# SW6208_A_A_B_LED__188.net
KiCad netlist of a schematic drawn in Altium Designer
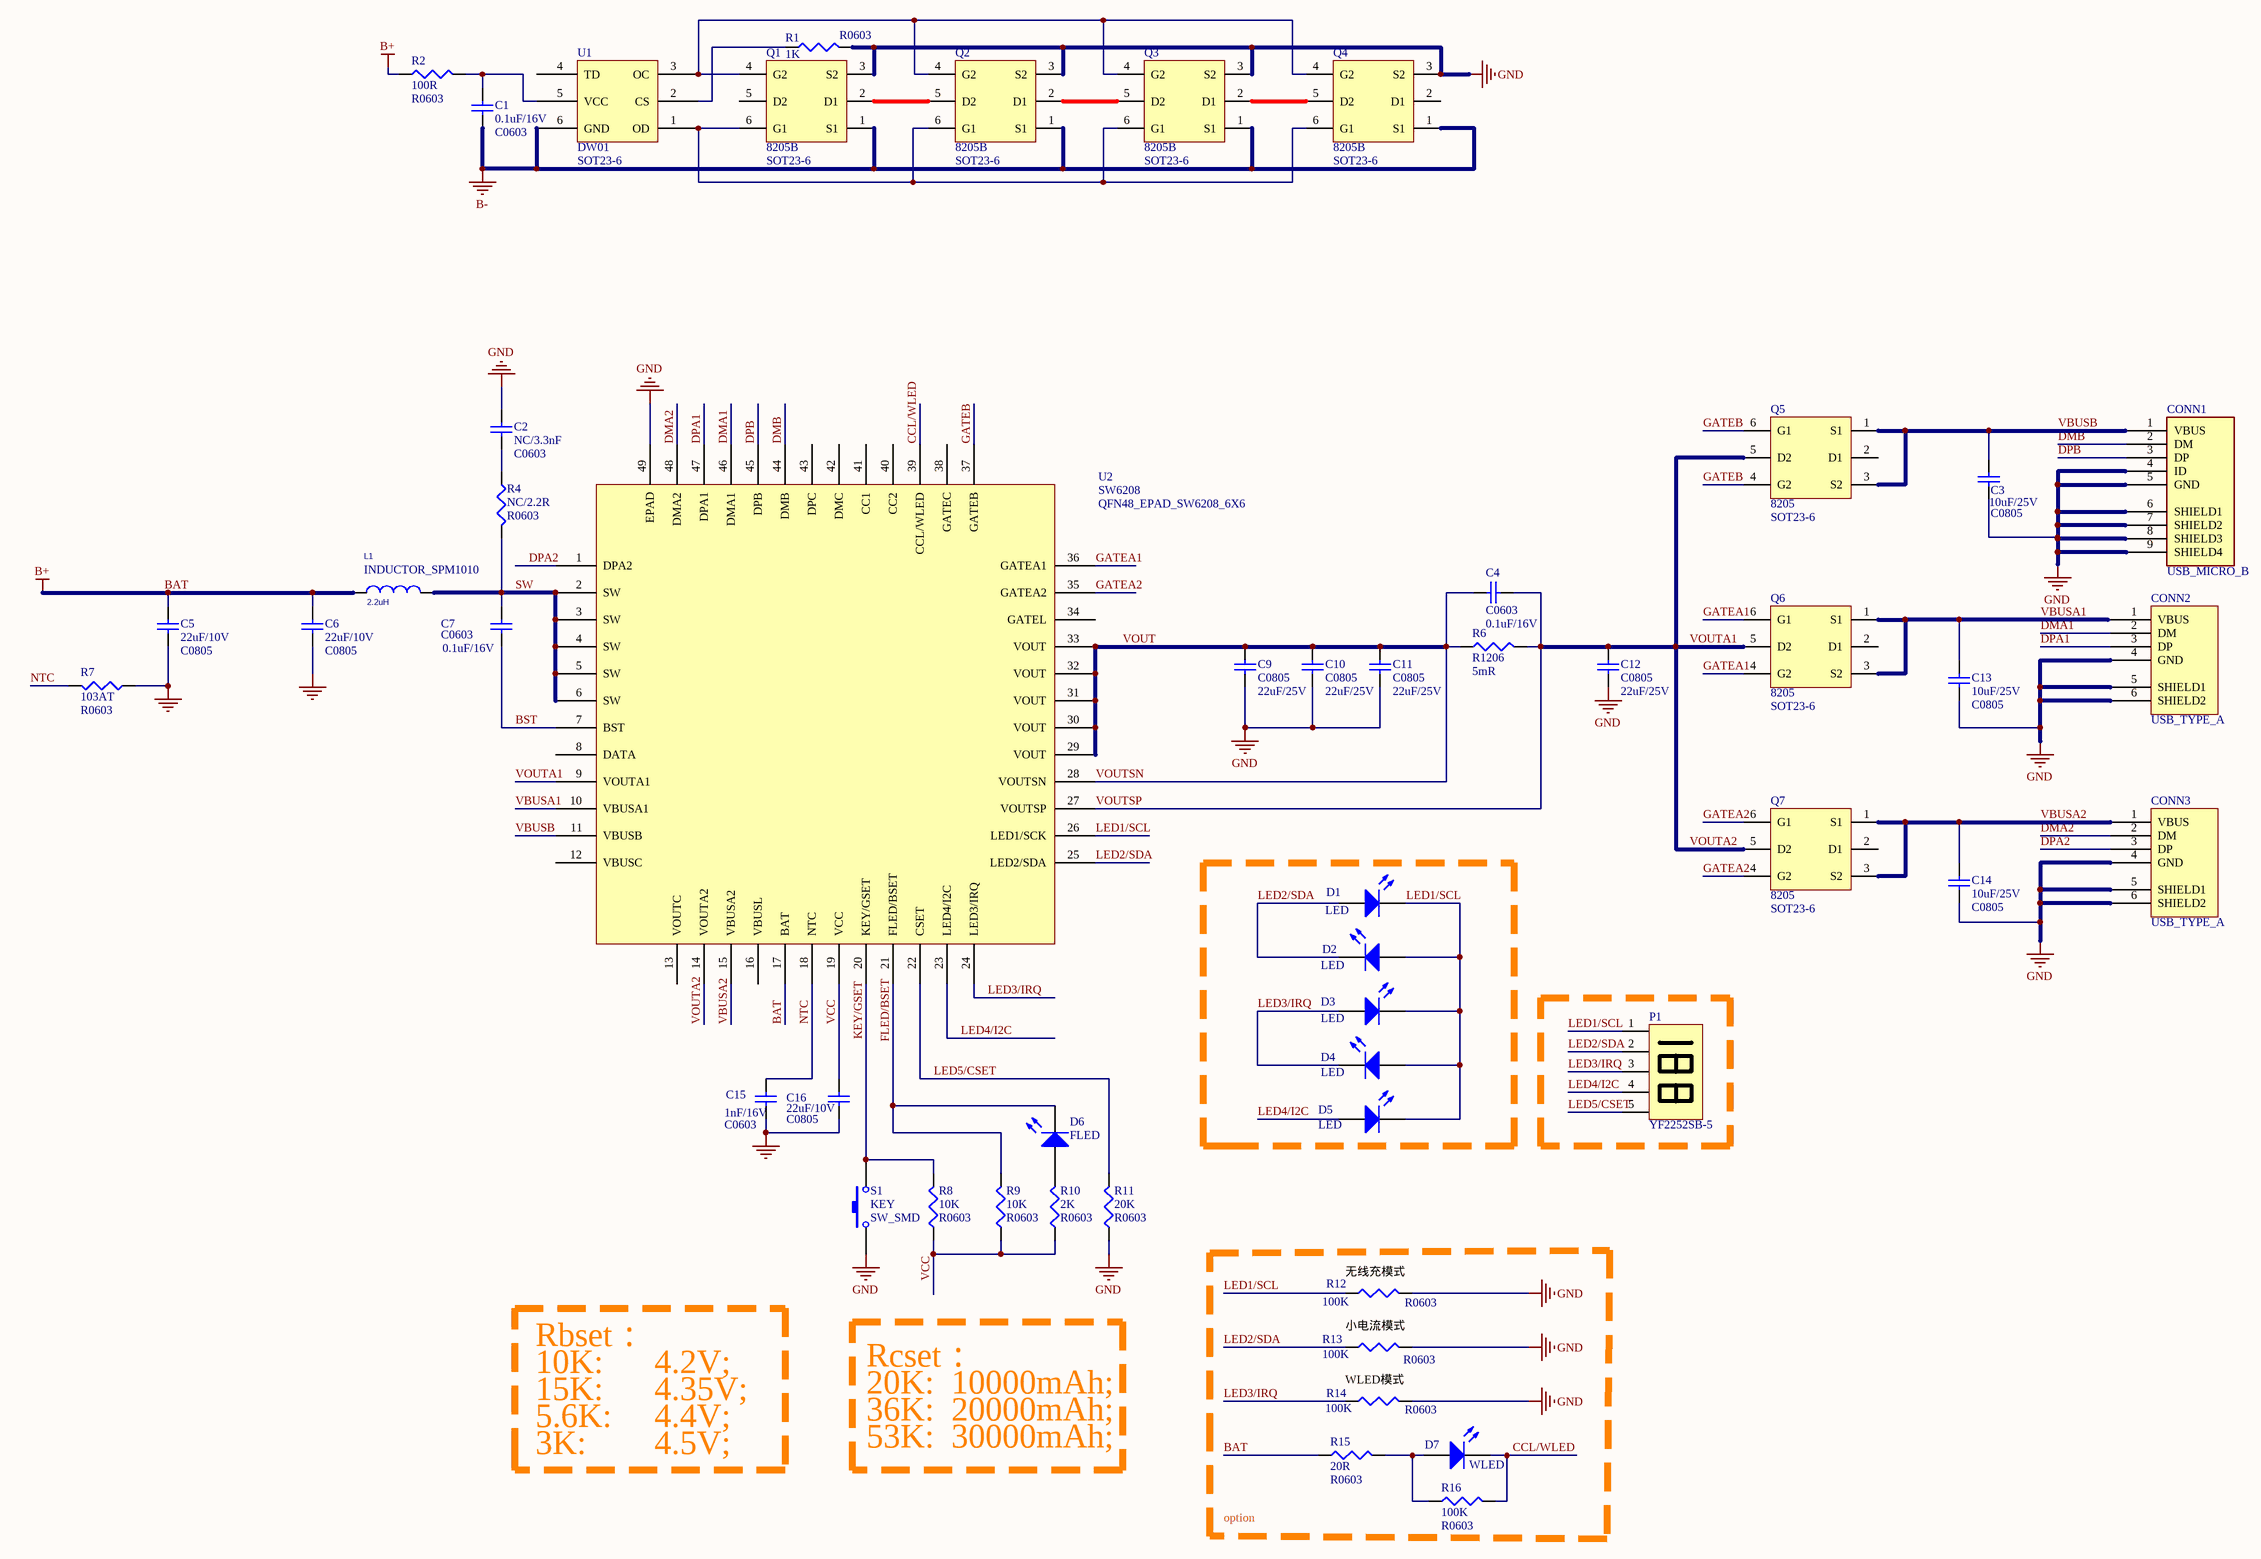
[diagram p0: SW6208+A+A+B+LED_普通188数码管.SchDoc]

(export (version "E")
  (design (tool "Eeschema 10.0.6"))
  (components
    (comp (ref "C1")
      (value "0.1uF/16V")
      (footprint "C0603")
      (description "Capacitor")
      (fields (field (name "PUBLISHER") "Altium Limited"))
      (libsource (lib "参考设计器件原理图更新") (part "CAP0603"))
    )
    (comp (ref "C2")
      (value "NC/3.3nF")
      (footprint "C0603")
      (description "Capacitor")
      (fields (field (name "PUBLISHER") "Altium Limited"))
      (libsource (lib "参考设计器件原理图更新") (part "CAP0603"))
    )
    (comp (ref "C3")
      (value "10uF/25V")
      (footprint "C0805")
      (description "Capacitor")
      (fields (field (name "PUBLISHER") "Altium Limited"))
      (libsource (lib "参考设计器件原理图更新") (part "CAP0805"))
    )
    (comp (ref "C4")
      (value "C0603")
      (footprint "C0603")
      (description "Capacitor")
      (fields (field (name "ALTIUM_VALUE") "0.1uF/16V") (field (name "PUBLISHER") "Altium Limited"))
      (libsource (lib "*") (part "CAP0603"))
    )
    (comp (ref "C5")
      (value "22uF/10V")
      (footprint "C0805")
      (description "Capacitor")
      (fields (field (name "PUBLISHER") "Altium Limited"))
      (libsource (lib "参考设计器件原理图更新") (part "CAP0805"))
    )
    (comp (ref "C6")
      (value "22uF/10V")
      (footprint "C0805")
      (description "Capacitor")
      (fields (field (name "PUBLISHER") "Altium Limited"))
      (libsource (lib "参考设计器件原理图更新") (part "CAP0805"))
    )
    (comp (ref "C7")
      (value "0.1uF/16V")
      (footprint "C0603")
      (description "Capacitor")
      (fields (field (name "PUBLISHER") "Altium Limited"))
      (libsource (lib "参考设计器件原理图更新") (part "CAP0603"))
    )
    (comp (ref "C9")
      (value "C0805")
      (footprint "C0805")
      (description "Capacitor")
      (fields (field (name "ALTIUM_VALUE") "22uF/25V") (field (name "PUBLISHER") "Altium Limited"))
      (libsource (lib "*") (part "CAP0805"))
    )
    (comp (ref "C10")
      (value "C0805")
      (footprint "C0805")
      (description "Capacitor")
      (fields (field (name "ALTIUM_VALUE") "22uF/25V") (field (name "PUBLISHER") "Altium Limited"))
      (libsource (lib "*") (part "CAP0805"))
    )
    (comp (ref "C11")
      (value "C0805")
      (footprint "C0805")
      (description "Capacitor")
      (fields (field (name "ALTIUM_VALUE") "22uF/25V") (field (name "PUBLISHER") "Altium Limited"))
      (libsource (lib "*") (part "CAP0805"))
    )
    (comp (ref "C12")
      (value "C0805")
      (footprint "C0805")
      (description "Capacitor")
      (fields (field (name "ALTIUM_VALUE") "22uF/25V") (field (name "PUBLISHER") "Altium Limited"))
      (libsource (lib "*") (part "CAP0805"))
    )
    (comp (ref "C13")
      (value "10uF/25V")
      (footprint "C0805")
      (description "Capacitor")
      (fields (field (name "PUBLISHER") "Altium Limited"))
      (libsource (lib "参考设计器件原理图更新") (part "CAP0805"))
    )
    (comp (ref "C14")
      (value "10uF/25V")
      (footprint "C0805")
      (description "Capacitor")
      (fields (field (name "PUBLISHER") "Altium Limited"))
      (libsource (lib "参考设计器件原理图更新") (part "CAP0805"))
    )
    (comp (ref "C15")
      (value "1nF/16V")
      (footprint "C0603")
      (description "Capacitor")
      (fields (field (name "PUBLISHER") "Altium Limited"))
      (libsource (lib "参考设计器件原理图更新") (part "CAP0603"))
    )
    (comp (ref "C16")
      (value "22uF/10V")
      (footprint "C0805")
      (description "Capacitor")
      (fields (field (name "PUBLISHER") "Altium Limited"))
      (libsource (lib "参考设计器件原理图更新") (part "CAP0805"))
    )
    (comp (ref "CONN1")
      (value "USB_MICRO_B")
      (footprint "USB_MICRO_B")
      (libsource (lib "参考设计器件原理图更新") (part "USB_MICRO_B"))
    )
    (comp (ref "CONN2")
      (value "USB_TYPE_A")
      (footprint "USB_TYPE_A")
      (libsource (lib "参考设计器件原理图更新") (part "USB_TYPE_A"))
    )
    (comp (ref "CONN3")
      (value "USB_TYPE_A")
      (footprint "USB_TYPE_A")
      (libsource (lib "参考设计器件原理图更新") (part "USB_TYPE_A"))
    )
    (comp (ref "D1")
      (value "LED")
      (footprint "LED0603")
      (fields (field (name "PUBLISHER") "Altium Limited"))
      (libsource (lib "参考设计器件原理图更新") (part "LED_0603"))
    )
    (comp (ref "D2")
      (value "LED")
      (footprint "LED0603")
      (fields (field (name "PUBLISHER") "Altium Limited"))
      (libsource (lib "参考设计器件原理图更新") (part "LED_0603"))
    )
    (comp (ref "D3")
      (value "LED")
      (footprint "LED0603")
      (fields (field (name "PUBLISHER") "Altium Limited"))
      (libsource (lib "参考设计器件原理图更新") (part "LED_0603"))
    )
    (comp (ref "D4")
      (value "LED")
      (footprint "LED0603")
      (fields (field (name "PUBLISHER") "Altium Limited"))
      (libsource (lib "参考设计器件原理图更新") (part "LED_0603"))
    )
    (comp (ref "D5")
      (value "LED")
      (footprint "LED0603")
      (fields (field (name "PUBLISHER") "Altium Limited"))
      (libsource (lib "参考设计器件原理图更新") (part "LED_0603"))
    )
    (comp (ref "D6")
      (value "FLED")
      (footprint "LED0603")
      (description "LED")
      (fields (field (name "PUBLISHER") "Altium Limited"))
      (libsource (lib "参考设计器件原理图更新") (part "LED_0603"))
    )
    (comp (ref "D7")
      (value "WLED")
      (footprint "LED_5MM")
      (fields (field (name "PUBLISHER") "Altium Limited"))
      (libsource (lib "参考设计器件原理图更新") (part "WLED"))
    )
    (comp (ref "L1")
      (value "2.2uH")
      (footprint "INDUCTOR_SPM1010")
      (description "INDUCTOR")
      (libsource (lib "参考设计器件原理图更新") (part "INDUCTOR_SPM1010"))
    )
    (comp (ref "P1")
      (value "YF2252SB-5")
      (footprint "LED_Display_5")
      (description "188_LED_Display")
      (libsource (lib "参考设计器件原理图更新") (part "LED_Display_5"))
    )
    (comp (ref "Q1")
      (value "8205B")
      (footprint "SOT23-6")
      (description "NMOS")
      (fields (field (name "FOOTPRINF") "SOT23-6"))
      (libsource (lib "参考设计器件原理图更新") (part "8205"))
    )
    (comp (ref "Q2")
      (value "8205B")
      (footprint "SOT23-6")
      (description "NMOS")
      (fields (field (name "FOOTPRINF") "SOT23-6"))
      (libsource (lib "参考设计器件原理图更新") (part "8205"))
    )
    (comp (ref "Q3")
      (value "8205B")
      (footprint "SOT23-6")
      (description "NMOS")
      (fields (field (name "FOOTPRINF") "SOT23-6"))
      (libsource (lib "参考设计器件原理图更新") (part "8205"))
    )
    (comp (ref "Q4")
      (value "8205B")
      (footprint "SOT23-6")
      (description "NMOS")
      (fields (field (name "FOOTPRINF") "SOT23-6"))
      (libsource (lib "参考设计器件原理图更新") (part "8205"))
    )
    (comp (ref "Q5")
      (value "8205")
      (footprint "SOT23-6")
      (description "NMOS")
      (fields (field (name "FOOTPRINF") "SOT23-6"))
      (libsource (lib "") (part "8205_1"))
    )
    (comp (ref "Q6")
      (value "8205")
      (footprint "SOT23-6")
      (description "NMOS")
      (fields (field (name "FOOTPRINF") "SOT23-6"))
      (libsource (lib "") (part "8205_1"))
    )
    (comp (ref "Q7")
      (value "8205")
      (footprint "SOT23-6")
      (description "NMOS")
      (fields (field (name "FOOTPRINF") "SOT23-6"))
      (libsource (lib "") (part "8205_1"))
    )
    (comp (ref "R1")
      (value "1K")
      (footprint "R0603")
      (description "Resistor")
      (fields (field (name "PUBLISHER") "Altium Limited"))
      (libsource (lib "参考设计器件原理图更新") (part "RES_0603"))
    )
    (comp (ref "R2")
      (value "100R")
      (footprint "R0603")
      (description "Resistor")
      (fields (field (name "PUBLISHER") "Altium Limited"))
      (libsource (lib "参考设计器件原理图更新") (part "RES_0603"))
    )
    (comp (ref "R4")
      (value "NC/2.2R")
      (footprint "R0603")
      (description "Resistor")
      (fields (field (name "PUBLISHER") "Altium Limited"))
      (libsource (lib "参考设计器件原理图更新") (part "RES_0603"))
    )
    (comp (ref "R6")
      (value "R1206")
      (footprint "1206")
      (description "Resistor")
      (fields (field (name "ALTIUM_VALUE") "5mR") (field (name "PUBLISHER") "Altium Limited"))
      (libsource (lib "*") (part "RES"))
    )
    (comp (ref "R7")
      (value "103AT")
      (footprint "R0603")
      (description "Resistor")
      (fields (field (name "PUBLISHER") "Altium Limited"))
      (libsource (lib "参考设计器件原理图更新") (part "RES_0603"))
    )
    (comp (ref "R8")
      (value "10K")
      (footprint "R0603")
      (description "Resistor")
      (fields (field (name "PUBLISHER") "Altium Limited"))
      (libsource (lib "参考设计器件原理图更新") (part "RES_0603"))
    )
    (comp (ref "R9")
      (value "10K")
      (footprint "R0603")
      (description "Resistor")
      (fields (field (name "PUBLISHER") "Altium Limited"))
      (libsource (lib "参考设计器件原理图更新") (part "RES_0603"))
    )
    (comp (ref "R10")
      (value "2K")
      (footprint "R0603")
      (description "Resistor")
      (fields (field (name "PUBLISHER") "Altium Limited"))
      (libsource (lib "参考设计器件原理图更新") (part "RES_0603"))
    )
    (comp (ref "R11")
      (value "20K")
      (footprint "R0603")
      (description "Resistor")
      (fields (field (name "PUBLISHER") "Altium Limited"))
      (libsource (lib "参考设计器件原理图更新") (part "RES_0603"))
    )
    (comp (ref "R12")
      (value "100K")
      (footprint "R0603")
      (description "Resistor")
      (fields (field (name "PUBLISHER") "Altium Limited"))
      (libsource (lib "参考设计器件原理图更新") (part "RES_0603"))
    )
    (comp (ref "R13")
      (value "100K")
      (footprint "R0603")
      (description "Resistor")
      (fields (field (name "PUBLISHER") "Altium Limited"))
      (libsource (lib "参考设计器件原理图更新") (part "RES_0603"))
    )
    (comp (ref "R14")
      (value "100K")
      (footprint "R0603")
      (description "Resistor")
      (fields (field (name "PUBLISHER") "Altium Limited"))
      (libsource (lib "参考设计器件原理图更新") (part "RES_0603"))
    )
    (comp (ref "R15")
      (value "20R")
      (footprint "R0603")
      (description "Resistor")
      (fields (field (name "PUBLISHER") "Altium Limited"))
      (libsource (lib "参考设计器件原理图更新") (part "RES_0603"))
    )
    (comp (ref "R16")
      (value "100K")
      (footprint "R0603")
      (description "Resistor")
      (fields (field (name "PUBLISHER") "Altium Limited"))
      (libsource (lib "参考设计器件原理图更新") (part "RES_0603"))
    )
    (comp (ref "S1")
      (value "KEY")
      (footprint "SW_SMD")
      (fields (field (name "FOOTPRINF") "SW_SMD"))
      (libsource (lib "参考设计器件原理图更新") (part "SW K"))
    )
    (comp (ref "U1")
      (value "DW01")
      (footprint "SOT23-6")
      (description "BAT_PROTECT_IC")
      (libsource (lib "参考设计器件原理图更新") (part "DW01"))
    )
    (comp (ref "U2")
      (value "SW6208")
      (footprint "QFN48_EPAD_SW6208_6X6")
      (description "IC")
      (libsource (lib "芯片型号原理图") (part "SW6208"))
    )
  )
  (nets
    (net (code "1") (name "/BST") (class "Default")
      (node (ref "C7") (pin "1") (pinfunction "1_1") (pintype "passive"))
      (node (ref "U2") (pin "7") (pinfunction "BST_7") (pintype "passive"))
    )
    (net (code "2") (name "/CCL{slash}WLED") (class "Default")
      (node (ref "D7") (pin "2") (pinfunction "K_2") (pintype "passive"))
      (node (ref "R16") (pin "2") (pinfunction "2_2") (pintype "passive"))
      (node (ref "U2") (pin "39") (pinfunction "CCL/WLED_39") (pintype "passive"))
    )
    (net (code "3") (name "/DMA1") (class "Default")
      (node (ref "CONN2") (pin "2") (pinfunction "DM_2") (pintype "passive"))
      (node (ref "U2") (pin "46") (pinfunction "DMA1_46") (pintype "passive"))
    )
    (net (code "4") (name "/DMA2") (class "Default")
      (node (ref "CONN3") (pin "2") (pinfunction "DM_2") (pintype "passive"))
      (node (ref "U2") (pin "48") (pinfunction "DMA2_48") (pintype "passive"))
    )
    (net (code "5") (name "/DMB") (class "Default")
      (node (ref "CONN1") (pin "2") (pinfunction "DM_2") (pintype "passive"))
      (node (ref "U2") (pin "44") (pinfunction "DMB_44") (pintype "passive"))
    )
    (net (code "6") (name "/DPA1") (class "Default")
      (node (ref "CONN2") (pin "3") (pinfunction "DP_3") (pintype "passive"))
      (node (ref "U2") (pin "47") (pinfunction "DPA1_47") (pintype "passive"))
    )
    (net (code "7") (name "/DPA2") (class "Default")
      (node (ref "CONN3") (pin "3") (pinfunction "DP_3") (pintype "passive"))
      (node (ref "U2") (pin "1") (pinfunction "DPA2_1") (pintype "passive"))
    )
    (net (code "8") (name "/DPB") (class "Default")
      (node (ref "CONN1") (pin "3") (pinfunction "DP_3") (pintype "passive"))
      (node (ref "U2") (pin "45") (pinfunction "DPB_45") (pintype "passive"))
    )
    (net (code "9") (name "/FLED{slash}BSET") (class "Default")
      (node (ref "D6") (pin "2") (pinfunction "K_2") (pintype "passive"))
      (node (ref "R9") (pin "2") (pinfunction "2_2") (pintype "passive"))
      (node (ref "U2") (pin "21") (pinfunction "FLED/BSET_21") (pintype "passive"))
    )
    (net (code "10") (name "/GATEA1") (class "Default")
      (node (ref "Q6") (pin "4") (pinfunction "G2_4") (pintype "passive"))
      (node (ref "Q6") (pin "6") (pinfunction "G1_6") (pintype "passive"))
      (node (ref "U2") (pin "36") (pinfunction "GATEA1_36") (pintype "passive"))
    )
    (net (code "11") (name "/GATEA2") (class "Default")
      (node (ref "Q7") (pin "4") (pinfunction "G2_4") (pintype "passive"))
      (node (ref "Q7") (pin "6") (pinfunction "G1_6") (pintype "passive"))
      (node (ref "U2") (pin "35") (pinfunction "GATEA2_35") (pintype "passive"))
    )
    (net (code "12") (name "/GATEB") (class "Default")
      (node (ref "Q5") (pin "4") (pinfunction "G2_4") (pintype "passive"))
      (node (ref "Q5") (pin "6") (pinfunction "G1_6") (pintype "passive"))
      (node (ref "U2") (pin "37") (pinfunction "GATEB_37") (pintype "passive"))
    )
    (net (code "13") (name "/KEY{slash}GSET") (class "Default")
      (node (ref "R8") (pin "2") (pinfunction "2_2") (pintype "passive"))
      (node (ref "S1") (pin "2") (pinfunction "2_2") (pintype "passive"))
      (node (ref "U2") (pin "20") (pinfunction "KEY/GSET_20") (pintype "passive"))
    )
    (net (code "14") (name "/LED1{slash}SCL") (class "Default")
      (node (ref "D1") (pin "2") (pinfunction "K_2") (pintype "passive"))
      (node (ref "D2") (pin "1") (pinfunction "A_1") (pintype "passive"))
      (node (ref "D3") (pin "2") (pinfunction "K_2") (pintype "passive"))
      (node (ref "D4") (pin "1") (pinfunction "A_1") (pintype "passive"))
      (node (ref "D5") (pin "2") (pinfunction "K_2") (pintype "passive"))
      (node (ref "P1") (pin "1") (pinfunction "F_1") (pintype "passive"))
      (node (ref "R12") (pin "1") (pinfunction "1_1") (pintype "passive"))
      (node (ref "U2") (pin "26") (pinfunction "LED1/SCK_26") (pintype "passive"))
    )
    (net (code "15") (name "/LED2{slash}SDA") (class "Default")
      (node (ref "D1") (pin "1") (pinfunction "A_1") (pintype "passive"))
      (node (ref "D2") (pin "2") (pinfunction "K_2") (pintype "passive"))
      (node (ref "P1") (pin "2") (pinfunction "C_2") (pintype "passive"))
      (node (ref "R13") (pin "1") (pinfunction "1_1") (pintype "passive"))
      (node (ref "U2") (pin "25") (pinfunction "LED2/SDA_25") (pintype "passive"))
    )
    (net (code "16") (name "/LED3{slash}IRQ") (class "Default")
      (node (ref "D3") (pin "1") (pinfunction "A_1") (pintype "passive"))
      (node (ref "D4") (pin "2") (pinfunction "K_2") (pintype "passive"))
      (node (ref "P1") (pin "3") (pinfunction "D_3") (pintype "passive"))
      (node (ref "R14") (pin "1") (pinfunction "1_1") (pintype "passive"))
      (node (ref "U2") (pin "24") (pinfunction "LED3/IRQ_24") (pintype "passive"))
    )
    (net (code "17") (name "/LED4{slash}I2C") (class "Default")
      (node (ref "D5") (pin "1") (pinfunction "A_1") (pintype "passive"))
      (node (ref "P1") (pin "4") (pinfunction "E_4") (pintype "passive"))
      (node (ref "U2") (pin "23") (pinfunction "LED4/I2C_23") (pintype "passive"))
    )
    (net (code "18") (name "/LED5{slash}CSET") (class "Default")
      (node (ref "P1") (pin "5") (pinfunction "G_5") (pintype "passive"))
      (node (ref "R11") (pin "2") (pinfunction "2_2") (pintype "passive"))
      (node (ref "U2") (pin "22") (pinfunction "CSET_22") (pintype "passive"))
    )
    (net (code "19") (name "/NTC") (class "Default")
      (node (ref "C15") (pin "1") (pinfunction "1_1") (pintype "passive"))
      (node (ref "R7") (pin "2") (pinfunction "2_2") (pintype "passive"))
      (node (ref "U2") (pin "18") (pinfunction "NTC_18") (pintype "passive"))
    )
    (net (code "20") (name "/SW") (class "Default")
      (node (ref "C7") (pin "2") (pinfunction "2_2") (pintype "passive"))
      (node (ref "L1") (pin "2") (pinfunction "2_2") (pintype "passive"))
      (node (ref "R4") (pin "2") (pinfunction "2_2") (pintype "passive"))
      (node (ref "U2") (pin "2") (pinfunction "SW_2") (pintype "passive"))
      (node (ref "U2") (pin "3") (pinfunction "SW_3") (pintype "passive"))
      (node (ref "U2") (pin "4") (pinfunction "SW_4") (pintype "passive"))
      (node (ref "U2") (pin "5") (pinfunction "SW_5") (pintype "passive"))
      (node (ref "U2") (pin "6") (pinfunction "SW_6") (pintype "passive"))
    )
    (net (code "21") (name "/VBUSA1") (class "Default")
      (node (ref "C13") (pin "2") (pinfunction "2_2") (pintype "passive"))
      (node (ref "CONN2") (pin "1") (pinfunction "VBUS_1") (pintype "passive"))
      (node (ref "Q6") (pin "1") (pinfunction "S1_1") (pintype "passive"))
      (node (ref "Q6") (pin "3") (pinfunction "S2_3") (pintype "passive"))
      (node (ref "U2") (pin "10") (pinfunction "VBUSA1_10") (pintype "passive"))
    )
    (net (code "22") (name "/VBUSA2") (class "Default")
      (node (ref "C14") (pin "2") (pinfunction "2_2") (pintype "passive"))
      (node (ref "CONN3") (pin "1") (pinfunction "VBUS_1") (pintype "passive"))
      (node (ref "Q7") (pin "1") (pinfunction "S1_1") (pintype "passive"))
      (node (ref "Q7") (pin "3") (pinfunction "S2_3") (pintype "passive"))
      (node (ref "U2") (pin "15") (pinfunction "VBUSA2_15") (pintype "passive"))
    )
    (net (code "23") (name "/VBUSB") (class "Default")
      (node (ref "C3") (pin "2") (pinfunction "2_2") (pintype "passive"))
      (node (ref "Q5") (pin "1") (pinfunction "S1_1") (pintype "passive"))
      (node (ref "Q5") (pin "3") (pinfunction "S2_3") (pintype "passive"))
      (node (ref "U2") (pin "11") (pinfunction "VBUSB_11") (pintype "passive"))
    )
    (net (code "24") (name "/VCC") (class "Default")
      (node (ref "C16") (pin "1") (pinfunction "1_1") (pintype "passive"))
      (node (ref "R10") (pin "1") (pinfunction "1_1") (pintype "passive"))
      (node (ref "R8") (pin "1") (pinfunction "1_1") (pintype "passive"))
      (node (ref "R9") (pin "1") (pinfunction "1_1") (pintype "passive"))
      (node (ref "U2") (pin "19") (pinfunction "VCC_19") (pintype "passive"))
    )
    (net (code "25") (name "/VOUT") (class "Default")
      (node (ref "C10") (pin "2") (pinfunction "2_2") (pintype "passive"))
      (node (ref "C11") (pin "2") (pinfunction "2_2") (pintype "passive"))
      (node (ref "C4") (pin "1") (pinfunction "1_1") (pintype "passive"))
      (node (ref "C9") (pin "2") (pinfunction "2_2") (pintype "passive"))
      (node (ref "R6") (pin "1") (pinfunction "1_1") (pintype "passive"))
      (node (ref "U2") (pin "28") (pinfunction "VOUTSN_28") (pintype "passive"))
      (node (ref "U2") (pin "29") (pinfunction "VOUT_29") (pintype "passive"))
      (node (ref "U2") (pin "30") (pinfunction "VOUT_30") (pintype "passive"))
      (node (ref "U2") (pin "31") (pinfunction "VOUT_31") (pintype "passive"))
      (node (ref "U2") (pin "32") (pinfunction "VOUT_32") (pintype "passive"))
      (node (ref "U2") (pin "33") (pinfunction "VOUT_33") (pintype "passive"))
    )
    (net (code "26") (name "/VOUTA1") (class "Default")
      (node (ref "C12") (pin "2") (pinfunction "2_2") (pintype "passive"))
      (node (ref "C4") (pin "2") (pinfunction "2_2") (pintype "passive"))
      (node (ref "Q5") (pin "5") (pinfunction "D2_5") (pintype "passive"))
      (node (ref "Q6") (pin "5") (pinfunction "D2_5") (pintype "passive"))
      (node (ref "Q7") (pin "5") (pinfunction "D2_5") (pintype "passive"))
      (node (ref "R6") (pin "2") (pinfunction "2_2") (pintype "passive"))
      (node (ref "U2") (pin "14") (pinfunction "VOUTA2_14") (pintype "passive"))
      (node (ref "U2") (pin "27") (pinfunction "VOUTSP_27") (pintype "passive"))
      (node (ref "U2") (pin "9") (pinfunction "VOUTA1_9") (pintype "passive"))
    )
    (net (code "27") (name "B+") (class "Default")
      (node (ref "C5") (pin "2") (pinfunction "2_2") (pintype "passive"))
      (node (ref "C6") (pin "2") (pinfunction "2_2") (pintype "passive"))
      (node (ref "L1") (pin "1") (pinfunction "1_1") (pintype "passive"))
      (node (ref "R15") (pin "1") (pinfunction "1_1") (pintype "passive"))
      (node (ref "R2") (pin "1") (pinfunction "1_1") (pintype "passive"))
      (node (ref "U2") (pin "17") (pinfunction "BAT_17") (pintype "passive"))
    )
    (net (code "28") (name "B-") (class "Default")
      (node (ref "C1") (pin "1") (pinfunction "1_1") (pintype "passive"))
      (node (ref "Q1") (pin "1") (pinfunction "S1_1") (pintype "passive"))
      (node (ref "Q2") (pin "1") (pinfunction "S1_1") (pintype "passive"))
      (node (ref "Q3") (pin "1") (pinfunction "S1_1") (pintype "passive"))
      (node (ref "Q4") (pin "1") (pinfunction "S1_1") (pintype "passive"))
      (node (ref "U1") (pin "6") (pinfunction "GND_6") (pintype "passive"))
    )
    (net (code "29") (name "GND") (class "Default")
      (node (ref "C10") (pin "1") (pinfunction "1_1") (pintype "passive"))
      (node (ref "C11") (pin "1") (pinfunction "1_1") (pintype "passive"))
      (node (ref "C12") (pin "1") (pinfunction "1_1") (pintype "passive"))
      (node (ref "C13") (pin "1") (pinfunction "1_1") (pintype "passive"))
      (node (ref "C14") (pin "1") (pinfunction "1_1") (pintype "passive"))
      (node (ref "C15") (pin "2") (pinfunction "2_2") (pintype "passive"))
      (node (ref "C16") (pin "2") (pinfunction "2_2") (pintype "passive"))
      (node (ref "C2") (pin "2") (pinfunction "2_2") (pintype "passive"))
      (node (ref "C3") (pin "1") (pinfunction "1_1") (pintype "passive"))
      (node (ref "C5") (pin "1") (pinfunction "1_1") (pintype "passive"))
      (node (ref "C6") (pin "1") (pinfunction "1_1") (pintype "passive"))
      (node (ref "C9") (pin "1") (pinfunction "1_1") (pintype "passive"))
      (node (ref "CONN1") (pin "9") (pinfunction "SHIELD4_9") (pintype "passive"))
      (node (ref "CONN2") (pin "4") (pinfunction "GND_4") (pintype "passive"))
      (node (ref "CONN2") (pin "5") (pinfunction "SHIELD1_5") (pintype "passive"))
      (node (ref "CONN2") (pin "6") (pinfunction "SHIELD2_6") (pintype "passive"))
      (node (ref "CONN3") (pin "4") (pinfunction "GND_4") (pintype "passive"))
      (node (ref "CONN3") (pin "5") (pinfunction "SHIELD1_5") (pintype "passive"))
      (node (ref "CONN3") (pin "6") (pinfunction "SHIELD2_6") (pintype "passive"))
      (node (ref "Q1") (pin "3") (pinfunction "S2_3") (pintype "passive"))
      (node (ref "Q2") (pin "3") (pinfunction "S2_3") (pintype "passive"))
      (node (ref "Q3") (pin "3") (pinfunction "S2_3") (pintype "passive"))
      (node (ref "Q4") (pin "3") (pinfunction "S2_3") (pintype "passive"))
      (node (ref "R1") (pin "2") (pinfunction "2_2") (pintype "passive"))
      (node (ref "R11") (pin "1") (pinfunction "1_1") (pintype "passive"))
      (node (ref "R12") (pin "2") (pinfunction "2_2") (pintype "passive"))
      (node (ref "R13") (pin "2") (pinfunction "2_2") (pintype "passive"))
      (node (ref "R14") (pin "2") (pinfunction "2_2") (pintype "passive"))
      (node (ref "R7") (pin "1") (pinfunction "1_1") (pintype "passive"))
      (node (ref "S1") (pin "1") (pinfunction "1_1") (pintype "passive"))
      (node (ref "U2") (pin "49") (pinfunction "EPAD_49") (pintype "passive"))
    )
    (net (code "30") (name "Net-(C2-Pad1)") (class "Default")
      (node (ref "C2") (pin "1") (pinfunction "1_1") (pintype "passive"))
      (node (ref "R4") (pin "1") (pinfunction "1_1") (pintype "passive"))
    )
    (net (code "31") (name "Net-(D6-A)") (class "Default")
      (node (ref "D6") (pin "1") (pinfunction "A_1") (pintype "passive"))
      (node (ref "R10") (pin "2") (pinfunction "2_2") (pintype "passive"))
    )
    (net (code "32") (name "Net-(D7-A)") (class "Default")
      (node (ref "D7") (pin "1") (pinfunction "A_1") (pintype "passive"))
      (node (ref "R15") (pin "2") (pinfunction "2_2") (pintype "passive"))
      (node (ref "R16") (pin "1") (pinfunction "1_1") (pintype "passive"))
    )
    (net (code "33") (name "Net-(Q1-D1)") (class "Default")
      (node (ref "Q1") (pin "2") (pinfunction "D1_2") (pintype "passive"))
      (node (ref "Q2") (pin "5") (pinfunction "D2_5") (pintype "passive"))
    )
    (net (code "34") (name "Net-(Q1-G1)") (class "Default")
      (node (ref "Q1") (pin "6") (pinfunction "G1_6") (pintype "passive"))
      (node (ref "Q2") (pin "6") (pinfunction "G1_6") (pintype "passive"))
      (node (ref "Q3") (pin "6") (pinfunction "G1_6") (pintype "passive"))
      (node (ref "Q4") (pin "6") (pinfunction "G1_6") (pintype "passive"))
      (node (ref "U1") (pin "1") (pinfunction "OD_1") (pintype "passive"))
    )
    (net (code "35") (name "Net-(Q1-G2)") (class "Default")
      (node (ref "Q1") (pin "4") (pinfunction "G2_4") (pintype "passive"))
      (node (ref "Q2") (pin "4") (pinfunction "G2_4") (pintype "passive"))
      (node (ref "Q3") (pin "4") (pinfunction "G2_4") (pintype "passive"))
      (node (ref "Q4") (pin "4") (pinfunction "G2_4") (pintype "passive"))
      (node (ref "U1") (pin "3") (pinfunction "OC_3") (pintype "passive"))
    )
    (net (code "36") (name "Net-(Q2-D1)") (class "Default")
      (node (ref "Q2") (pin "2") (pinfunction "D1_2") (pintype "passive"))
      (node (ref "Q3") (pin "5") (pinfunction "D2_5") (pintype "passive"))
    )
    (net (code "37") (name "Net-(Q3-D1)") (class "Default")
      (node (ref "Q3") (pin "2") (pinfunction "D1_2") (pintype "passive"))
      (node (ref "Q4") (pin "5") (pinfunction "D2_5") (pintype "passive"))
    )
    (net (code "38") (name "Net-(U1-CS)") (class "Default")
      (node (ref "R1") (pin "1") (pinfunction "1_1") (pintype "passive"))
      (node (ref "U1") (pin "2") (pinfunction "CS_2") (pintype "passive"))
    )
    (net (code "39") (name "Net-(U1-VCC)") (class "Default")
      (node (ref "C1") (pin "2") (pinfunction "2_2") (pintype "passive"))
      (node (ref "R2") (pin "2") (pinfunction "2_2") (pintype "passive"))
      (node (ref "U1") (pin "5") (pinfunction "VCC_5") (pintype "passive"))
    )
    (net (code "40") (name "unconnected-(CONN1-GND-Pad5)") (class "Default")
      (node (ref "CONN1") (pin "5") (pinfunction "GND_5") (pintype "passive"))
    )
    (net (code "41") (name "unconnected-(CONN1-ID-Pad4)") (class "Default")
      (node (ref "CONN1") (pin "4") (pinfunction "ID_4") (pintype "passive"))
    )
    (net (code "42") (name "unconnected-(CONN1-SHIELD1-Pad6)") (class "Default")
      (node (ref "CONN1") (pin "6") (pinfunction "SHIELD1_6") (pintype "passive"))
    )
    (net (code "43") (name "unconnected-(CONN1-SHIELD2-Pad7)") (class "Default")
      (node (ref "CONN1") (pin "7") (pinfunction "SHIELD2_7") (pintype "passive"))
    )
    (net (code "44") (name "unconnected-(CONN1-SHIELD3-Pad8)") (class "Default")
      (node (ref "CONN1") (pin "8") (pinfunction "SHIELD3_8") (pintype "passive"))
    )
    (net (code "45") (name "unconnected-(CONN1-VBUS-Pad1)") (class "Default")
      (node (ref "CONN1") (pin "1") (pinfunction "VBUS_1") (pintype "passive"))
    )
    (net (code "46") (name "unconnected-(Q1-D2-Pad5)") (class "Default")
      (node (ref "Q1") (pin "5") (pinfunction "D2_5") (pintype "passive"))
    )
    (net (code "47") (name "unconnected-(Q4-D1-Pad2)") (class "Default")
      (node (ref "Q4") (pin "2") (pinfunction "D1_2") (pintype "passive"))
    )
    (net (code "48") (name "unconnected-(Q5-D1-Pad2)") (class "Default")
      (node (ref "Q5") (pin "2") (pinfunction "D1_2") (pintype "passive"))
    )
    (net (code "49") (name "unconnected-(Q6-D1-Pad2)") (class "Default")
      (node (ref "Q6") (pin "2") (pinfunction "D1_2") (pintype "passive"))
    )
    (net (code "50") (name "unconnected-(Q7-D1-Pad2)") (class "Default")
      (node (ref "Q7") (pin "2") (pinfunction "D1_2") (pintype "passive"))
    )
    (net (code "51") (name "unconnected-(U1-TD-Pad4)") (class "Default")
      (node (ref "U1") (pin "4") (pinfunction "TD_4") (pintype "passive"))
    )
    (net (code "52") (name "unconnected-(U2-CC1-Pad41)") (class "Default")
      (node (ref "U2") (pin "41") (pinfunction "CC1_41") (pintype "passive"))
    )
    (net (code "53") (name "unconnected-(U2-CC2-Pad40)") (class "Default")
      (node (ref "U2") (pin "40") (pinfunction "CC2_40") (pintype "passive"))
    )
    (net (code "54") (name "unconnected-(U2-DATA-Pad8)") (class "Default")
      (node (ref "U2") (pin "8") (pinfunction "DATA_8") (pintype "passive"))
    )
    (net (code "55") (name "unconnected-(U2-DMC-Pad42)") (class "Default")
      (node (ref "U2") (pin "42") (pinfunction "DMC_42") (pintype "passive"))
    )
    (net (code "56") (name "unconnected-(U2-DPC-Pad43)") (class "Default")
      (node (ref "U2") (pin "43") (pinfunction "DPC_43") (pintype "passive"))
    )
    (net (code "57") (name "unconnected-(U2-GATEC-Pad38)") (class "Default")
      (node (ref "U2") (pin "38") (pinfunction "GATEC_38") (pintype "passive"))
    )
    (net (code "58") (name "unconnected-(U2-GATEL-Pad34)") (class "Default")
      (node (ref "U2") (pin "34") (pinfunction "GATEL_34") (pintype "passive"))
    )
    (net (code "59") (name "unconnected-(U2-VBUSC-Pad12)") (class "Default")
      (node (ref "U2") (pin "12") (pinfunction "VBUSC_12") (pintype "passive"))
    )
    (net (code "60") (name "unconnected-(U2-VBUSL-Pad16)") (class "Default")
      (node (ref "U2") (pin "16") (pinfunction "VBUSL_16") (pintype "passive"))
    )
    (net (code "61") (name "unconnected-(U2-VOUTC-Pad13)") (class "Default")
      (node (ref "U2") (pin "13") (pinfunction "VOUTC_13") (pintype "passive"))
    )
  )
)
